# Board_3.net
KiCad netlist of a schematic drawn in EAGLE
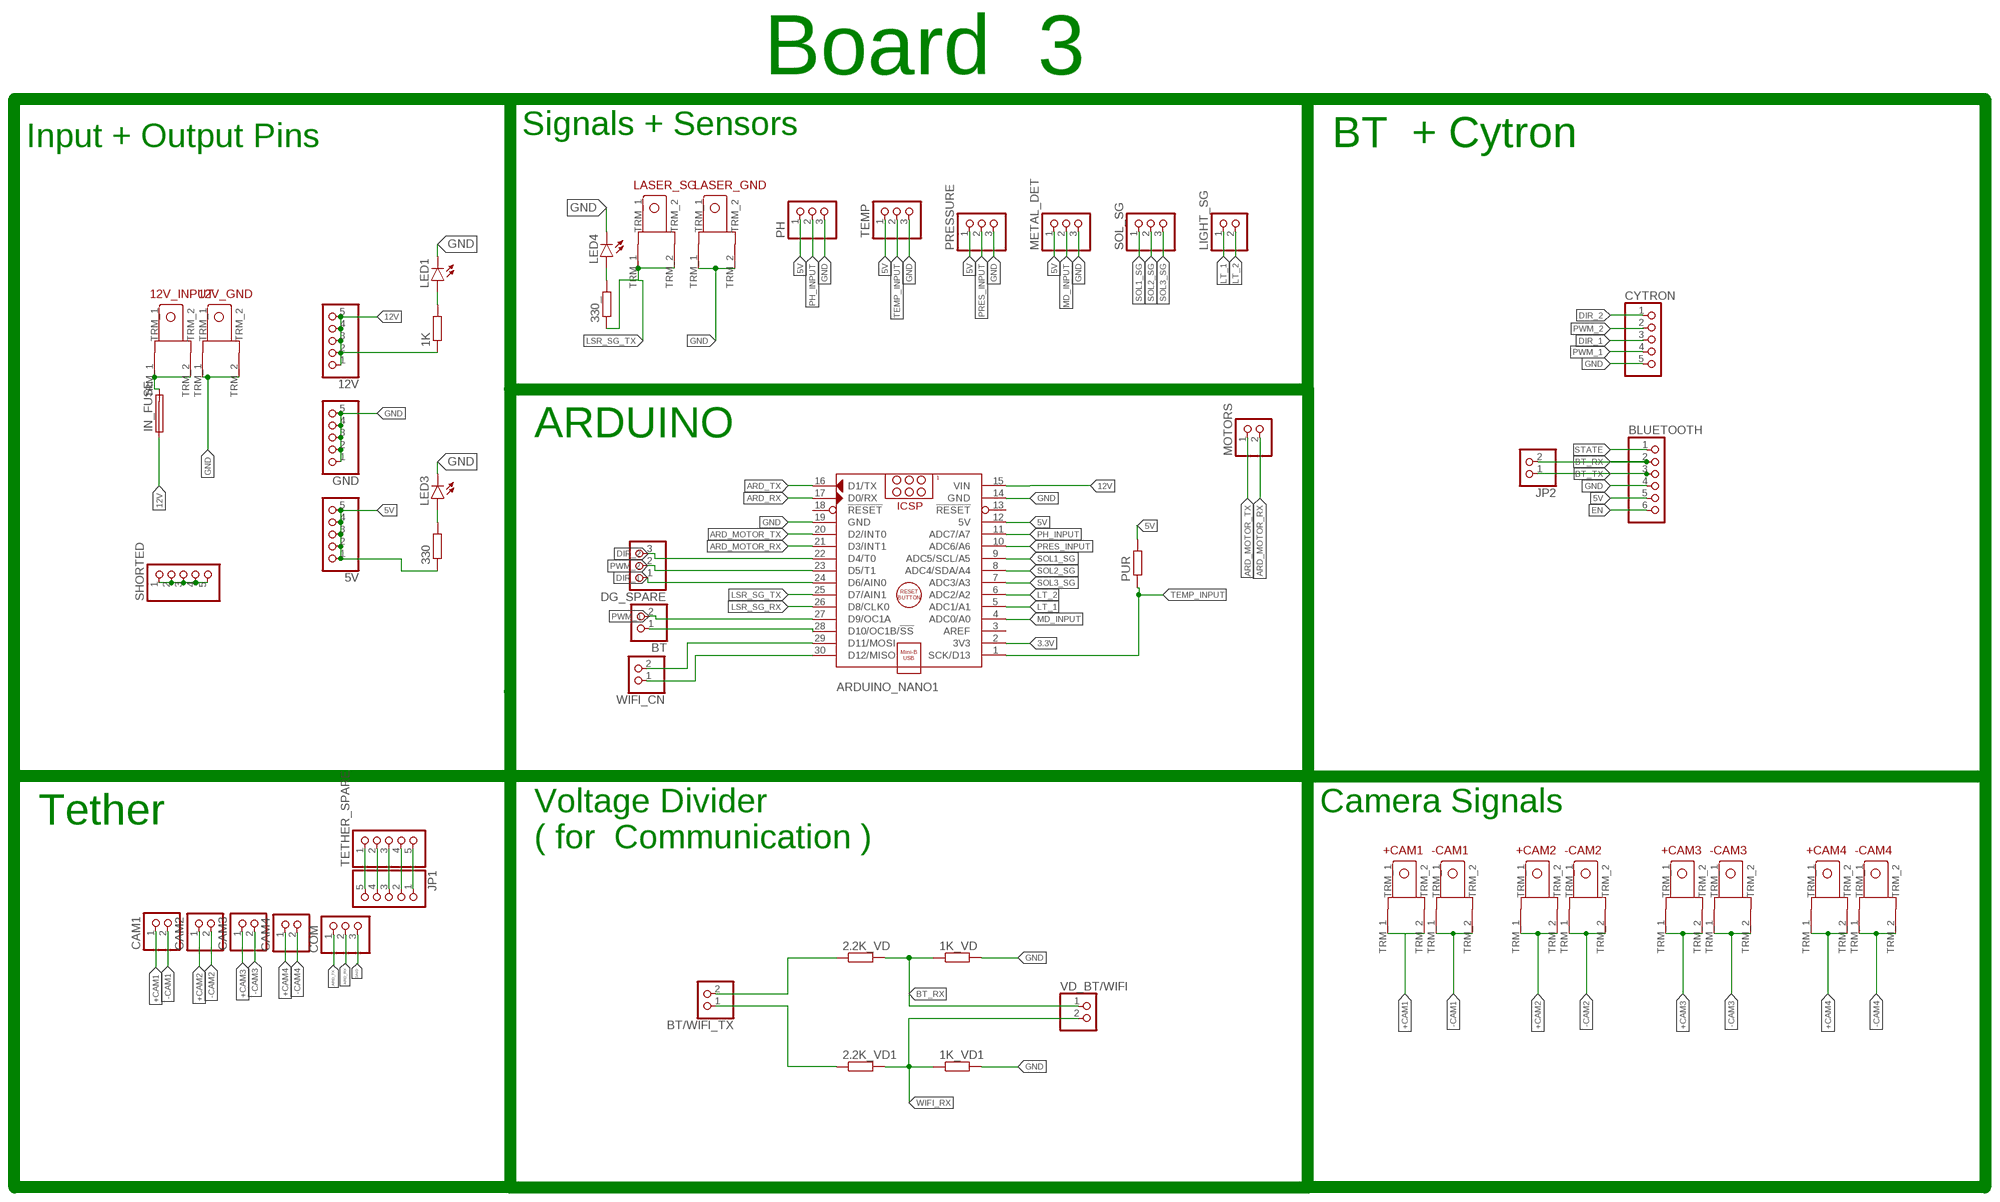
[diagram p0: schematic, sheet 1]

(export (version "E")
  (design (tool "Eeschema 10.0.6"))
  (components
    (comp (ref "+CAM1")
      (value "TERMINAL_EDITED")
      (footprint "eagle-import:TERMINAL_EDITED")
      (libsource (lib "eagle-import") (part "TERMINAL_EDITED"))
    )
    (comp (ref "+CAM2")
      (value "TERMINAL_EDITED")
      (footprint "eagle-import:TERMINAL_EDITED")
      (libsource (lib "eagle-import") (part "TERMINAL_EDITED"))
    )
    (comp (ref "+CAM3")
      (value "TERMINAL_EDITED")
      (footprint "eagle-import:TERMINAL_EDITED")
      (libsource (lib "eagle-import") (part "TERMINAL_EDITED"))
    )
    (comp (ref "+CAM4")
      (value "TERMINAL_EDITED")
      (footprint "eagle-import:TERMINAL_EDITED")
      (libsource (lib "eagle-import") (part "TERMINAL_EDITED"))
    )
    (comp (ref "-CAM1")
      (value "TERMINAL_EDITED")
      (footprint "eagle-import:TERMINAL_EDITED")
      (libsource (lib "eagle-import") (part "TERMINAL_EDITED"))
    )
    (comp (ref "-CAM2")
      (value "TERMINAL_EDITED")
      (footprint "eagle-import:TERMINAL_EDITED")
      (libsource (lib "eagle-import") (part "TERMINAL_EDITED"))
    )
    (comp (ref "-CAM3")
      (value "TERMINAL_EDITED")
      (footprint "eagle-import:TERMINAL_EDITED")
      (libsource (lib "eagle-import") (part "TERMINAL_EDITED"))
    )
    (comp (ref "-CAM4")
      (value "TERMINAL_EDITED")
      (footprint "eagle-import:TERMINAL_EDITED")
      (libsource (lib "eagle-import") (part "TERMINAL_EDITED"))
    )
    (comp (ref "1K")
      (value "RESISTOR")
      (footprint "eagle-import:0207_10")
      (libsource (lib "eagle-import") (part "RESISTOR"))
    )
    (comp (ref "1K_VD")
      (value "RESISTOR")
      (footprint "eagle-import:0207_10")
      (libsource (lib "eagle-import") (part "RESISTOR"))
    )
    (comp (ref "1K_VD1")
      (value "RESISTOR")
      (footprint "eagle-import:0207_10")
      (libsource (lib "eagle-import") (part "RESISTOR"))
    )
    (comp (ref "2.2K_VD")
      (value "RESISTOR")
      (footprint "eagle-import:0207_10")
      (libsource (lib "eagle-import") (part "RESISTOR"))
    )
    (comp (ref "2.2K_VD1")
      (value "RESISTOR")
      (footprint "eagle-import:0207_10")
      (libsource (lib "eagle-import") (part "RESISTOR"))
    )
    (comp (ref "5V")
      (value "PINHD-1X5")
      (footprint "eagle-import:1X05")
      (libsource (lib "eagle-import") (part "PINHD-1X5"))
    )
    (comp (ref "12V")
      (value "PINHD-1X5")
      (footprint "eagle-import:1X05")
      (libsource (lib "eagle-import") (part "PINHD-1X5"))
    )
    (comp (ref "12V_GND")
      (value "TERMINAL_EDITED")
      (footprint "eagle-import:TERMINAL_EDITED")
      (libsource (lib "eagle-import") (part "TERMINAL_EDITED"))
    )
    (comp (ref "12V_INPUT")
      (value "TERMINAL_EDITED")
      (footprint "eagle-import:TERMINAL_EDITED")
      (libsource (lib "eagle-import") (part "TERMINAL_EDITED"))
    )
    (comp (ref "330")
      (value "RESISTOR")
      (footprint "eagle-import:0207_10")
      (libsource (lib "eagle-import") (part "RESISTOR"))
    )
    (comp (ref "330_")
      (value "RESISTOR")
      (footprint "eagle-import:0207_10")
      (libsource (lib "eagle-import") (part "RESISTOR"))
    )
    (comp (ref "ARDUINO_NANO1")
      (value "ARDUINO_NANO")
      (footprint "eagle-import:ARDUINO_NANO")
      (libsource (lib "eagle-import") (part "ARDUINO_NANO"))
    )
    (comp (ref "BLUETOOTH")
      (value "BLUETOOTH_HC-05")
      (footprint "eagle-import:1X06")
      (libsource (lib "eagle-import") (part "BLUETOOTH_HC-05"))
    )
    (comp (ref "BT")
      (value "PINHD-1X2")
      (footprint "eagle-import:1X02")
      (libsource (lib "eagle-import") (part "PINHD-1X2"))
    )
    (comp (ref "BT/WIFI_TX")
      (value "PINHD-1X2")
      (footprint "eagle-import:1X02")
      (libsource (lib "eagle-import") (part "PINHD-1X2"))
    )
    (comp (ref "CAM1")
      (value "PINHD-1X2")
      (footprint "eagle-import:1X02")
      (libsource (lib "eagle-import") (part "PINHD-1X2"))
    )
    (comp (ref "CAM2")
      (value "PINHD-1X2")
      (footprint "eagle-import:1X02")
      (libsource (lib "eagle-import") (part "PINHD-1X2"))
    )
    (comp (ref "CAM3")
      (value "PINHD-1X2")
      (footprint "eagle-import:1X02")
      (libsource (lib "eagle-import") (part "PINHD-1X2"))
    )
    (comp (ref "CAM4")
      (value "PINHD-1X2")
      (footprint "eagle-import:1X02")
      (libsource (lib "eagle-import") (part "PINHD-1X2"))
    )
    (comp (ref "COM")
      (value "PINHD-1X3")
      (footprint "eagle-import:1X03")
      (libsource (lib "eagle-import") (part "PINHD-1X3"))
    )
    (comp (ref "CYTRON")
      (value "PINHD-1X5")
      (footprint "eagle-import:1X05")
      (libsource (lib "eagle-import") (part "PINHD-1X5"))
    )
    (comp (ref "DG_SPARE")
      (value "PINHD-1X3")
      (footprint "eagle-import:1X03")
      (libsource (lib "eagle-import") (part "PINHD-1X3"))
    )
    (comp (ref "GND")
      (value "PINHD-1X5")
      (footprint "eagle-import:1X05")
      (libsource (lib "eagle-import") (part "PINHD-1X5"))
    )
    (comp (ref "IN_FUSE")
      (value "FUSE")
      (footprint "eagle-import:SH22,5A")
      (libsource (lib "eagle-import") (part "FUSE"))
    )
    (comp (ref "JP1")
      (value "PINHD-1X5")
      (footprint "eagle-import:1X05")
      (libsource (lib "eagle-import") (part "PINHD-1X5"))
    )
    (comp (ref "JP2")
      (value "PINHD-1X2")
      (footprint "eagle-import:1X02")
      (libsource (lib "eagle-import") (part "PINHD-1X2"))
    )
    (comp (ref "LASER_GND")
      (value "TERMINAL_EDITED")
      (footprint "eagle-import:TERMINAL_EDITED")
      (libsource (lib "eagle-import") (part "TERMINAL_EDITED"))
    )
    (comp (ref "LASER_SG")
      (value "TERMINAL_EDITED")
      (footprint "eagle-import:TERMINAL_EDITED")
      (libsource (lib "eagle-import") (part "TERMINAL_EDITED"))
    )
    (comp (ref "LED1")
      (value "LED5MM")
      (footprint "eagle-import:LED5MM")
      (libsource (lib "eagle-import") (part "LED5MM"))
    )
    (comp (ref "LED3")
      (value "LED5MM")
      (footprint "eagle-import:LED5MM")
      (libsource (lib "eagle-import") (part "LED5MM"))
    )
    (comp (ref "LED4")
      (value "LED5MM")
      (footprint "eagle-import:LED5MM")
      (libsource (lib "eagle-import") (part "LED5MM"))
    )
    (comp (ref "LIGHT_SG")
      (value "PINHD-1X2")
      (footprint "eagle-import:1X02")
      (libsource (lib "eagle-import") (part "PINHD-1X2"))
    )
    (comp (ref "METAL_DET")
      (value "PINHD-1X3")
      (footprint "eagle-import:1X03")
      (libsource (lib "eagle-import") (part "PINHD-1X3"))
    )
    (comp (ref "MOTORS")
      (value "PINHD-1X2")
      (footprint "eagle-import:1X02")
      (libsource (lib "eagle-import") (part "PINHD-1X2"))
    )
    (comp (ref "PH")
      (value "PINHD-1X3")
      (footprint "eagle-import:1X03")
      (libsource (lib "eagle-import") (part "PINHD-1X3"))
    )
    (comp (ref "PRESSURE")
      (value "PINHD-1X3")
      (footprint "eagle-import:1X03")
      (libsource (lib "eagle-import") (part "PINHD-1X3"))
    )
    (comp (ref "PUR")
      (value "RESISTOR")
      (footprint "eagle-import:0207_10")
      (libsource (lib "eagle-import") (part "RESISTOR"))
    )
    (comp (ref "SHORTED")
      (value "PINHD-1X5")
      (footprint "eagle-import:1X05")
      (libsource (lib "eagle-import") (part "PINHD-1X5"))
    )
    (comp (ref "SOL_SG")
      (value "PINHD-1X3")
      (footprint "eagle-import:1X03")
      (libsource (lib "eagle-import") (part "PINHD-1X3"))
    )
    (comp (ref "TEMP")
      (value "PINHD-1X3")
      (footprint "eagle-import:1X03")
      (libsource (lib "eagle-import") (part "PINHD-1X3"))
    )
    (comp (ref "TETHER_SPARE")
      (value "PINHD-1X5")
      (footprint "eagle-import:1X05")
      (libsource (lib "eagle-import") (part "PINHD-1X5"))
    )
    (comp (ref "VD_BT/WIFI")
      (value "PINHD-1X2")
      (footprint "eagle-import:1X02")
      (libsource (lib "eagle-import") (part "PINHD-1X2"))
    )
    (comp (ref "WIFI_CN")
      (value "PINHD-1X2")
      (footprint "eagle-import:1X02")
      (libsource (lib "eagle-import") (part "PINHD-1X2"))
    )
  )
  (nets
    (net (code "1") (name "+CAM1") (class "Default")
      (node (ref "+CAM1") (pin "TRM_1") (pinfunction "TRM_1_TRM_1") (pintype "bidirectional"))
      (node (ref "+CAM1") (pin "TRM_2") (pinfunction "TRM_2_TRM_2") (pintype "bidirectional"))
      (node (ref "CAM1") (pin "1") (pinfunction "1_1") (pintype "passive"))
    )
    (net (code "2") (name "+CAM2") (class "Default")
      (node (ref "+CAM2") (pin "TRM_1") (pinfunction "TRM_1_TRM_1") (pintype "bidirectional"))
      (node (ref "+CAM2") (pin "TRM_2") (pinfunction "TRM_2_TRM_2") (pintype "bidirectional"))
      (node (ref "CAM2") (pin "1") (pinfunction "1_1") (pintype "passive"))
    )
    (net (code "3") (name "+CAM3") (class "Default")
      (node (ref "+CAM3") (pin "TRM_1") (pinfunction "TRM_1_TRM_1") (pintype "bidirectional"))
      (node (ref "+CAM3") (pin "TRM_2") (pinfunction "TRM_2_TRM_2") (pintype "bidirectional"))
      (node (ref "CAM3") (pin "1") (pinfunction "1_1") (pintype "passive"))
    )
    (net (code "4") (name "+CAM4") (class "Default")
      (node (ref "+CAM4") (pin "TRM_1") (pinfunction "TRM_1_TRM_1") (pintype "bidirectional"))
      (node (ref "+CAM4") (pin "TRM_2") (pinfunction "TRM_2_TRM_2") (pintype "bidirectional"))
      (node (ref "CAM4") (pin "1") (pinfunction "1_1") (pintype "passive"))
    )
    (net (code "5") (name "-CAM1") (class "Default")
      (node (ref "-CAM1") (pin "TRM_1") (pinfunction "TRM_1_TRM_1") (pintype "bidirectional"))
      (node (ref "-CAM1") (pin "TRM_2") (pinfunction "TRM_2_TRM_2") (pintype "bidirectional"))
      (node (ref "CAM1") (pin "2") (pinfunction "2_2") (pintype "passive"))
    )
    (net (code "6") (name "-CAM2") (class "Default")
      (node (ref "-CAM2") (pin "TRM_1") (pinfunction "TRM_1_TRM_1") (pintype "bidirectional"))
      (node (ref "-CAM2") (pin "TRM_2") (pinfunction "TRM_2_TRM_2") (pintype "bidirectional"))
      (node (ref "CAM2") (pin "2") (pinfunction "2_2") (pintype "passive"))
    )
    (net (code "7") (name "-CAM3") (class "Default")
      (node (ref "-CAM3") (pin "TRM_1") (pinfunction "TRM_1_TRM_1") (pintype "bidirectional"))
      (node (ref "-CAM3") (pin "TRM_2") (pinfunction "TRM_2_TRM_2") (pintype "bidirectional"))
      (node (ref "CAM3") (pin "2") (pinfunction "2_2") (pintype "passive"))
    )
    (net (code "8") (name "-CAM4") (class "Default")
      (node (ref "-CAM4") (pin "TRM_1") (pinfunction "TRM_1_TRM_1") (pintype "bidirectional"))
      (node (ref "-CAM4") (pin "TRM_2") (pinfunction "TRM_2_TRM_2") (pintype "bidirectional"))
      (node (ref "CAM4") (pin "2") (pinfunction "2_2") (pintype "passive"))
    )
    (net (code "9") (name "3.3V") (class "Default")
      (node (ref "ARDUINO_NANO1") (pin "2") (pinfunction "3V3_2") (pintype "output"))
    )
    (net (code "10") (name "5V") (class "Default")
      (node (ref "330") (pin "1") (pinfunction "1_1") (pintype "passive"))
      (node (ref "5V") (pin "1") (pinfunction "1_1") (pintype "passive"))
      (node (ref "5V") (pin "2") (pinfunction "2_2") (pintype "passive"))
      (node (ref "5V") (pin "3") (pinfunction "3_3") (pintype "passive"))
      (node (ref "5V") (pin "4") (pinfunction "4_4") (pintype "passive"))
      (node (ref "5V") (pin "5") (pinfunction "5_5") (pintype "passive"))
      (node (ref "ARDUINO_NANO1") (pin "12") (pinfunction "5V_12") (pintype "power_in"))
      (node (ref "BLUETOOTH") (pin "5") (pinfunction "5_5") (pintype "passive"))
      (node (ref "METAL_DET") (pin "1") (pinfunction "1_1") (pintype "passive"))
      (node (ref "PH") (pin "1") (pinfunction "1_1") (pintype "passive"))
      (node (ref "PRESSURE") (pin "1") (pinfunction "1_1") (pintype "passive"))
      (node (ref "PUR") (pin "2") (pinfunction "2_2") (pintype "passive"))
      (node (ref "TEMP") (pin "1") (pinfunction "1_1") (pintype "passive"))
    )
    (net (code "11") (name "12V") (class "Default")
      (node (ref "12V") (pin "1") (pinfunction "1_1") (pintype "passive"))
      (node (ref "12V") (pin "2") (pinfunction "2_2") (pintype "passive"))
      (node (ref "12V") (pin "3") (pinfunction "3_3") (pintype "passive"))
      (node (ref "12V") (pin "4") (pinfunction "4_4") (pintype "passive"))
      (node (ref "12V") (pin "5") (pinfunction "5_5") (pintype "passive"))
      (node (ref "1K") (pin "1") (pinfunction "1_1") (pintype "passive"))
      (node (ref "ARDUINO_NANO1") (pin "15") (pinfunction "VIN_15") (pintype "power_in"))
      (node (ref "IN_FUSE") (pin "1") (pinfunction "1_1") (pintype "passive"))
    )
    (net (code "12") (name "ARD_MOTOR_RX") (class "Default")
      (node (ref "ARDUINO_NANO1") (pin "21") (pinfunction "D3/INT1_21") (pintype "bidirectional"))
      (node (ref "MOTORS") (pin "2") (pinfunction "2_2") (pintype "passive"))
    )
    (net (code "13") (name "ARD_MOTOR_TX") (class "Default")
      (node (ref "ARDUINO_NANO1") (pin "20") (pinfunction "D2/INT0_20") (pintype "bidirectional"))
      (node (ref "MOTORS") (pin "1") (pinfunction "1_1") (pintype "passive"))
    )
    (net (code "14") (name "ARD_RX") (class "Default")
      (node (ref "ARDUINO_NANO1") (pin "17") (pinfunction "D0/RX_17") (pintype "bidirectional"))
      (node (ref "COM") (pin "2") (pinfunction "2_2") (pintype "passive"))
    )
    (net (code "15") (name "ARD_TX") (class "Default")
      (node (ref "ARDUINO_NANO1") (pin "16") (pinfunction "D1/TX_16") (pintype "bidirectional"))
      (node (ref "COM") (pin "1") (pinfunction "1_1") (pintype "passive"))
    )
    (net (code "16") (name "BT_RX") (class "Default")
      (node (ref "1K_VD") (pin "1") (pinfunction "1_1") (pintype "passive"))
      (node (ref "2.2K_VD") (pin "2") (pinfunction "2_2") (pintype "passive"))
      (node (ref "BLUETOOTH") (pin "2") (pinfunction "2_2") (pintype "passive"))
      (node (ref "JP2") (pin "2") (pinfunction "2_2") (pintype "passive"))
      (node (ref "VD_BT/WIFI") (pin "1") (pinfunction "1_1") (pintype "passive"))
    )
    (net (code "17") (name "BT_TX") (class "Default")
      (node (ref "BLUETOOTH") (pin "3") (pinfunction "3_3") (pintype "passive"))
      (node (ref "JP2") (pin "1") (pinfunction "1_1") (pintype "passive"))
    )
    (net (code "18") (name "DIR_1") (class "Default")
      (node (ref "ARDUINO_NANO1") (pin "24") (pinfunction "D6/AIN0_24") (pintype "bidirectional"))
      (node (ref "CYTRON") (pin "3") (pinfunction "3_3") (pintype "passive"))
      (node (ref "DG_SPARE") (pin "1") (pinfunction "1_1") (pintype "passive"))
    )
    (net (code "19") (name "DIR_2") (class "Default")
      (node (ref "ARDUINO_NANO1") (pin "22") (pinfunction "D4/T0_22") (pintype "bidirectional"))
      (node (ref "CYTRON") (pin "1") (pinfunction "1_1") (pintype "passive"))
      (node (ref "DG_SPARE") (pin "3") (pinfunction "3_3") (pintype "passive"))
    )
    (net (code "20") (name "EN") (class "Default")
      (node (ref "BLUETOOTH") (pin "6") (pinfunction "6_6") (pintype "passive"))
    )
    (net (code "21") (name "GND") (class "Default")
      (node (ref "12V_GND") (pin "TRM_1") (pinfunction "TRM_1_TRM_1") (pintype "bidirectional"))
      (node (ref "12V_GND") (pin "TRM_2") (pinfunction "TRM_2_TRM_2") (pintype "bidirectional"))
      (node (ref "1K_VD") (pin "2") (pinfunction "2_2") (pintype "passive"))
      (node (ref "1K_VD1") (pin "2") (pinfunction "2_2") (pintype "passive"))
      (node (ref "ARDUINO_NANO1") (pin "14") (pinfunction "GND_14") (pintype "power_in"))
      (node (ref "ARDUINO_NANO1") (pin "19") (pinfunction "GND_19") (pintype "power_in"))
      (node (ref "BLUETOOTH") (pin "4") (pinfunction "4_4") (pintype "passive"))
      (node (ref "COM") (pin "3") (pinfunction "3_3") (pintype "passive"))
      (node (ref "CYTRON") (pin "5") (pinfunction "5_5") (pintype "passive"))
      (node (ref "GND") (pin "1") (pinfunction "1_1") (pintype "passive"))
      (node (ref "GND") (pin "2") (pinfunction "2_2") (pintype "passive"))
      (node (ref "GND") (pin "3") (pinfunction "3_3") (pintype "passive"))
      (node (ref "GND") (pin "4") (pinfunction "4_4") (pintype "passive"))
      (node (ref "GND") (pin "5") (pinfunction "5_5") (pintype "passive"))
      (node (ref "LASER_GND") (pin "TRM_1") (pinfunction "TRM_1_TRM_1") (pintype "bidirectional"))
      (node (ref "LASER_GND") (pin "TRM_2") (pinfunction "TRM_2_TRM_2") (pintype "bidirectional"))
      (node (ref "LED1") (pin "K") (pinfunction "C_K") (pintype "passive"))
      (node (ref "LED3") (pin "K") (pinfunction "C_K") (pintype "passive"))
      (node (ref "LED4") (pin "K") (pinfunction "C_K") (pintype "passive"))
      (node (ref "METAL_DET") (pin "3") (pinfunction "3_3") (pintype "passive"))
      (node (ref "PH") (pin "3") (pinfunction "3_3") (pintype "passive"))
      (node (ref "PRESSURE") (pin "3") (pinfunction "3_3") (pintype "passive"))
      (node (ref "TEMP") (pin "3") (pinfunction "3_3") (pintype "passive"))
    )
    (net (code "22") (name "LSR_SG_RX") (class "Default")
      (node (ref "ARDUINO_NANO1") (pin "26") (pinfunction "D8/CLK0_26") (pintype "bidirectional"))
    )
    (net (code "23") (name "LSR_SG_TX") (class "Default")
      (node (ref "330_") (pin "1") (pinfunction "1_1") (pintype "passive"))
      (node (ref "ARDUINO_NANO1") (pin "25") (pinfunction "D7/AIN1_25") (pintype "bidirectional"))
      (node (ref "LASER_SG") (pin "TRM_1") (pinfunction "TRM_1_TRM_1") (pintype "bidirectional"))
      (node (ref "LASER_SG") (pin "TRM_2") (pinfunction "TRM_2_TRM_2") (pintype "bidirectional"))
    )
    (net (code "24") (name "LT_1") (class "Default")
      (node (ref "ARDUINO_NANO1") (pin "5") (pinfunction "ADC1/A1_5") (pintype "bidirectional"))
      (node (ref "LIGHT_SG") (pin "1") (pinfunction "1_1") (pintype "passive"))
    )
    (net (code "25") (name "LT_2") (class "Default")
      (node (ref "ARDUINO_NANO1") (pin "6") (pinfunction "ADC2/A2_6") (pintype "bidirectional"))
      (node (ref "LIGHT_SG") (pin "2") (pinfunction "2_2") (pintype "passive"))
    )
    (net (code "26") (name "MD_INPUT") (class "Default")
      (node (ref "ARDUINO_NANO1") (pin "4") (pinfunction "ADC0/A0_4") (pintype "bidirectional"))
      (node (ref "METAL_DET") (pin "2") (pinfunction "2_2") (pintype "passive"))
    )
    (net (code "27") (name "Net-(1K-Pad2)") (class "Default")
      (node (ref "1K") (pin "2") (pinfunction "2_2") (pintype "passive"))
      (node (ref "LED1") (pin "A") (pinfunction "A_A") (pintype "passive"))
    )
    (net (code "28") (name "Net-(2.2K_VD-Pad1)") (class "Default")
      (node (ref "2.2K_VD") (pin "1") (pinfunction "1_1") (pintype "passive"))
      (node (ref "BT/WIFI_TX") (pin "2") (pinfunction "2_2") (pintype "passive"))
    )
    (net (code "29") (name "Net-(2.2K_VD1-Pad1)") (class "Default")
      (node (ref "2.2K_VD1") (pin "1") (pinfunction "1_1") (pintype "passive"))
      (node (ref "BT/WIFI_TX") (pin "1") (pinfunction "1_1") (pintype "passive"))
    )
    (net (code "30") (name "Net-(12V_INPUT-PadTRM_1)") (class "Default")
      (node (ref "12V_INPUT") (pin "TRM_1") (pinfunction "TRM_1_TRM_1") (pintype "bidirectional"))
      (node (ref "12V_INPUT") (pin "TRM_2") (pinfunction "TRM_2_TRM_2") (pintype "bidirectional"))
      (node (ref "IN_FUSE") (pin "2") (pinfunction "2_2") (pintype "passive"))
    )
    (net (code "31") (name "Net-(330-Pad2)") (class "Default")
      (node (ref "330") (pin "2") (pinfunction "2_2") (pintype "passive"))
      (node (ref "LED3") (pin "A") (pinfunction "A_A") (pintype "passive"))
    )
    (net (code "32") (name "Net-(330_-Pad2)") (class "Default")
      (node (ref "330_") (pin "2") (pinfunction "2_2") (pintype "passive"))
      (node (ref "LED4") (pin "A") (pinfunction "A_A") (pintype "passive"))
    )
    (net (code "33") (name "Net-(ARDUINO_NANO1-D10{slash}OC1B{slash}~{SS})") (class "Default")
      (node (ref "ARDUINO_NANO1") (pin "28") (pinfunction "D10/OC1B/~{SS}_28") (pintype "bidirectional"))
      (node (ref "BT") (pin "1") (pinfunction "1_1") (pintype "passive"))
    )
    (net (code "34") (name "Net-(ARDUINO_NANO1-D11{slash}MOSI)") (class "Default")
      (node (ref "ARDUINO_NANO1") (pin "29") (pinfunction "D11/MOSI_29") (pintype "bidirectional"))
      (node (ref "WIFI_CN") (pin "2") (pinfunction "2_2") (pintype "passive"))
    )
    (net (code "35") (name "Net-(ARDUINO_NANO1-D12{slash}MISO)") (class "Default")
      (node (ref "ARDUINO_NANO1") (pin "30") (pinfunction "D12/MISO_30") (pintype "bidirectional"))
      (node (ref "WIFI_CN") (pin "1") (pinfunction "1_1") (pintype "passive"))
    )
    (net (code "36") (name "Net-(JP1-Pad1)") (class "Default")
      (node (ref "JP1") (pin "1") (pinfunction "1_1") (pintype "passive"))
      (node (ref "TETHER_SPARE") (pin "5") (pinfunction "5_5") (pintype "passive"))
    )
    (net (code "37") (name "Net-(JP1-Pad2)") (class "Default")
      (node (ref "JP1") (pin "2") (pinfunction "2_2") (pintype "passive"))
      (node (ref "TETHER_SPARE") (pin "4") (pinfunction "4_4") (pintype "passive"))
    )
    (net (code "38") (name "Net-(JP1-Pad3)") (class "Default")
      (node (ref "JP1") (pin "3") (pinfunction "3_3") (pintype "passive"))
      (node (ref "TETHER_SPARE") (pin "3") (pinfunction "3_3") (pintype "passive"))
    )
    (net (code "39") (name "Net-(JP1-Pad4)") (class "Default")
      (node (ref "JP1") (pin "4") (pinfunction "4_4") (pintype "passive"))
      (node (ref "TETHER_SPARE") (pin "2") (pinfunction "2_2") (pintype "passive"))
    )
    (net (code "40") (name "Net-(JP1-Pad5)") (class "Default")
      (node (ref "JP1") (pin "5") (pinfunction "5_5") (pintype "passive"))
      (node (ref "TETHER_SPARE") (pin "1") (pinfunction "1_1") (pintype "passive"))
    )
    (net (code "41") (name "Net-(SHORTED-Pad1)") (class "Default")
      (node (ref "SHORTED") (pin "1") (pinfunction "1_1") (pintype "passive"))
      (node (ref "SHORTED") (pin "2") (pinfunction "2_2") (pintype "passive"))
      (node (ref "SHORTED") (pin "3") (pinfunction "3_3") (pintype "passive"))
      (node (ref "SHORTED") (pin "4") (pinfunction "4_4") (pintype "passive"))
      (node (ref "SHORTED") (pin "5") (pinfunction "5_5") (pintype "passive"))
    )
    (net (code "42") (name "PH_INPUT") (class "Default")
      (node (ref "ARDUINO_NANO1") (pin "11") (pinfunction "ADC7/A7_11") (pintype "bidirectional"))
      (node (ref "PH") (pin "2") (pinfunction "2_2") (pintype "passive"))
    )
    (net (code "43") (name "PRES_INPUT") (class "Default")
      (node (ref "ARDUINO_NANO1") (pin "10") (pinfunction "ADC6/A6_10") (pintype "bidirectional"))
      (node (ref "PRESSURE") (pin "2") (pinfunction "2_2") (pintype "passive"))
    )
    (net (code "44") (name "PWM_1") (class "Default")
      (node (ref "ARDUINO_NANO1") (pin "27") (pinfunction "D9/OC1A_27") (pintype "bidirectional"))
      (node (ref "BT") (pin "2") (pinfunction "2_2") (pintype "passive"))
      (node (ref "CYTRON") (pin "4") (pinfunction "4_4") (pintype "passive"))
    )
    (net (code "45") (name "PWM_2") (class "Default")
      (node (ref "ARDUINO_NANO1") (pin "23") (pinfunction "D5/T1_23") (pintype "bidirectional"))
      (node (ref "CYTRON") (pin "2") (pinfunction "2_2") (pintype "passive"))
      (node (ref "DG_SPARE") (pin "2") (pinfunction "2_2") (pintype "passive"))
    )
    (net (code "46") (name "SOL1_SG") (class "Default")
      (node (ref "ARDUINO_NANO1") (pin "9") (pinfunction "ADC5/SCL/A5_9") (pintype "bidirectional"))
      (node (ref "SOL_SG") (pin "1") (pinfunction "1_1") (pintype "passive"))
    )
    (net (code "47") (name "SOL2_SG") (class "Default")
      (node (ref "ARDUINO_NANO1") (pin "8") (pinfunction "ADC4/SDA/A4_8") (pintype "bidirectional"))
      (node (ref "SOL_SG") (pin "2") (pinfunction "2_2") (pintype "passive"))
    )
    (net (code "48") (name "SOL3_SG") (class "Default")
      (node (ref "ARDUINO_NANO1") (pin "7") (pinfunction "ADC3/A3_7") (pintype "bidirectional"))
      (node (ref "SOL_SG") (pin "3") (pinfunction "3_3") (pintype "passive"))
    )
    (net (code "49") (name "STATE") (class "Default")
      (node (ref "BLUETOOTH") (pin "1") (pinfunction "1_1") (pintype "passive"))
    )
    (net (code "50") (name "TEMP_INPUT") (class "Default")
      (node (ref "ARDUINO_NANO1") (pin "1") (pinfunction "SCK/D13_1") (pintype "bidirectional"))
      (node (ref "PUR") (pin "1") (pinfunction "1_1") (pintype "passive"))
      (node (ref "TEMP") (pin "2") (pinfunction "2_2") (pintype "passive"))
    )
    (net (code "51") (name "WIFI_RX") (class "Default")
      (node (ref "1K_VD1") (pin "1") (pinfunction "1_1") (pintype "passive"))
      (node (ref "2.2K_VD1") (pin "2") (pinfunction "2_2") (pintype "passive"))
      (node (ref "VD_BT/WIFI") (pin "2") (pinfunction "2_2") (pintype "passive"))
    )
    (net (code "52") (name "unconnected-(ARDUINO_NANO1-AREF-Pad3)") (class "Default")
      (node (ref "ARDUINO_NANO1") (pin "3") (pinfunction "AREF_3") (pintype "input"))
    )
    (net (code "53") (name "unconnected-(ARDUINO_NANO1-~{RESET}-Pad13)") (class "Default")
      (node (ref "ARDUINO_NANO1") (pin "13") (pinfunction "~{RESET}_13") (pintype "input"))
    )
    (net (code "54") (name "unconnected-(ARDUINO_NANO1-~{RESET}-Pad18)") (class "Default")
      (node (ref "ARDUINO_NANO1") (pin "18") (pinfunction "~{RESET}_18") (pintype "input"))
    )
  )
)
